# led_power_decoupling.net
KiCad netlist of a schematic drawn in EAGLE
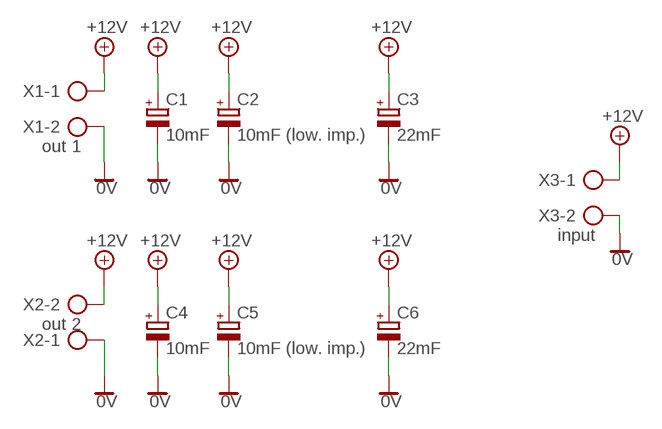
[diagram p0: schematic, sheet 1]

(export (version "E")
  (design (tool "Eeschema 10.0.6"))
  (components
    (comp (ref "C1")
      (value "10mF")
      (footprint "eagle-import:E7,5-16")
      (libsource (lib "eagle-import") (part "CPOL-EUE7.5-16"))
    )
    (comp (ref "C2")
      (value "10mF (low. imp.)")
      (footprint "eagle-import:E7,5-18")
      (libsource (lib "eagle-import") (part "CPOL-EUE7.5-18"))
    )
    (comp (ref "C3")
      (value "22mF")
      (footprint "eagle-import:EB25D")
      (libsource (lib "eagle-import") (part "CPOL-EUE10-25"))
    )
    (comp (ref "C4")
      (value "10mF")
      (footprint "eagle-import:E7,5-16")
      (libsource (lib "eagle-import") (part "CPOL-EUE7.5-16"))
    )
    (comp (ref "C5")
      (value "10mF (low. imp.)")
      (footprint "eagle-import:E7,5-18")
      (libsource (lib "eagle-import") (part "CPOL-EUE7.5-18"))
    )
    (comp (ref "C6")
      (value "22mF")
      (footprint "eagle-import:EB25D")
      (libsource (lib "eagle-import") (part "CPOL-EUE10-25"))
    )
    (comp (ref "X1")
      (value "out 1")
      (footprint "eagle-import:AK500_2")
      (libsource (lib "eagle-import") (part "AK500/2"))
    )
    (comp (ref "X2")
      (value "out 2")
      (footprint "eagle-import:AK500_2")
      (libsource (lib "eagle-import") (part "AK500/2"))
    )
    (comp (ref "X3")
      (value "input")
      (footprint "eagle-import:AK500_2")
      (libsource (lib "eagle-import") (part "AK500/2"))
    )
  )
  (nets
    (net (code "1") (name "+12V") (class "Default")
      (node (ref "C1") (pin "+") (pinfunction "+_+") (pintype "passive"))
      (node (ref "C2") (pin "+") (pinfunction "+_+") (pintype "passive"))
      (node (ref "C3") (pin "+") (pinfunction "+_+") (pintype "passive"))
      (node (ref "C4") (pin "+") (pinfunction "+_+") (pintype "passive"))
      (node (ref "C5") (pin "+") (pinfunction "+_+") (pintype "passive"))
      (node (ref "C6") (pin "+") (pinfunction "+_+") (pintype "passive"))
      (node (ref "X1") (pin "1") (pinfunction "KL_1") (pintype "passive"))
      (node (ref "X2") (pin "2") (pinfunction "KL_2") (pintype "passive"))
      (node (ref "X3") (pin "1") (pinfunction "KL_1") (pintype "passive"))
    )
    (net (code "2") (name "0V") (class "Default")
      (node (ref "C1") (pin "-") (pinfunction "-_-") (pintype "passive"))
      (node (ref "C2") (pin "-") (pinfunction "-_-") (pintype "passive"))
      (node (ref "C3") (pin "-") (pinfunction "-_-") (pintype "passive"))
      (node (ref "C4") (pin "-") (pinfunction "-_-") (pintype "passive"))
      (node (ref "C5") (pin "-") (pinfunction "-_-") (pintype "passive"))
      (node (ref "C6") (pin "-") (pinfunction "-_-") (pintype "passive"))
      (node (ref "X1") (pin "2") (pinfunction "KL_2") (pintype "passive"))
      (node (ref "X2") (pin "1") (pinfunction "KL_1") (pintype "passive"))
      (node (ref "X3") (pin "2") (pinfunction "KL_2") (pintype "passive"))
    )
  )
)
